# microzed_sd_v0_3_bdec564d.net
KiCad netlist of a schematic drawn in EAGLE
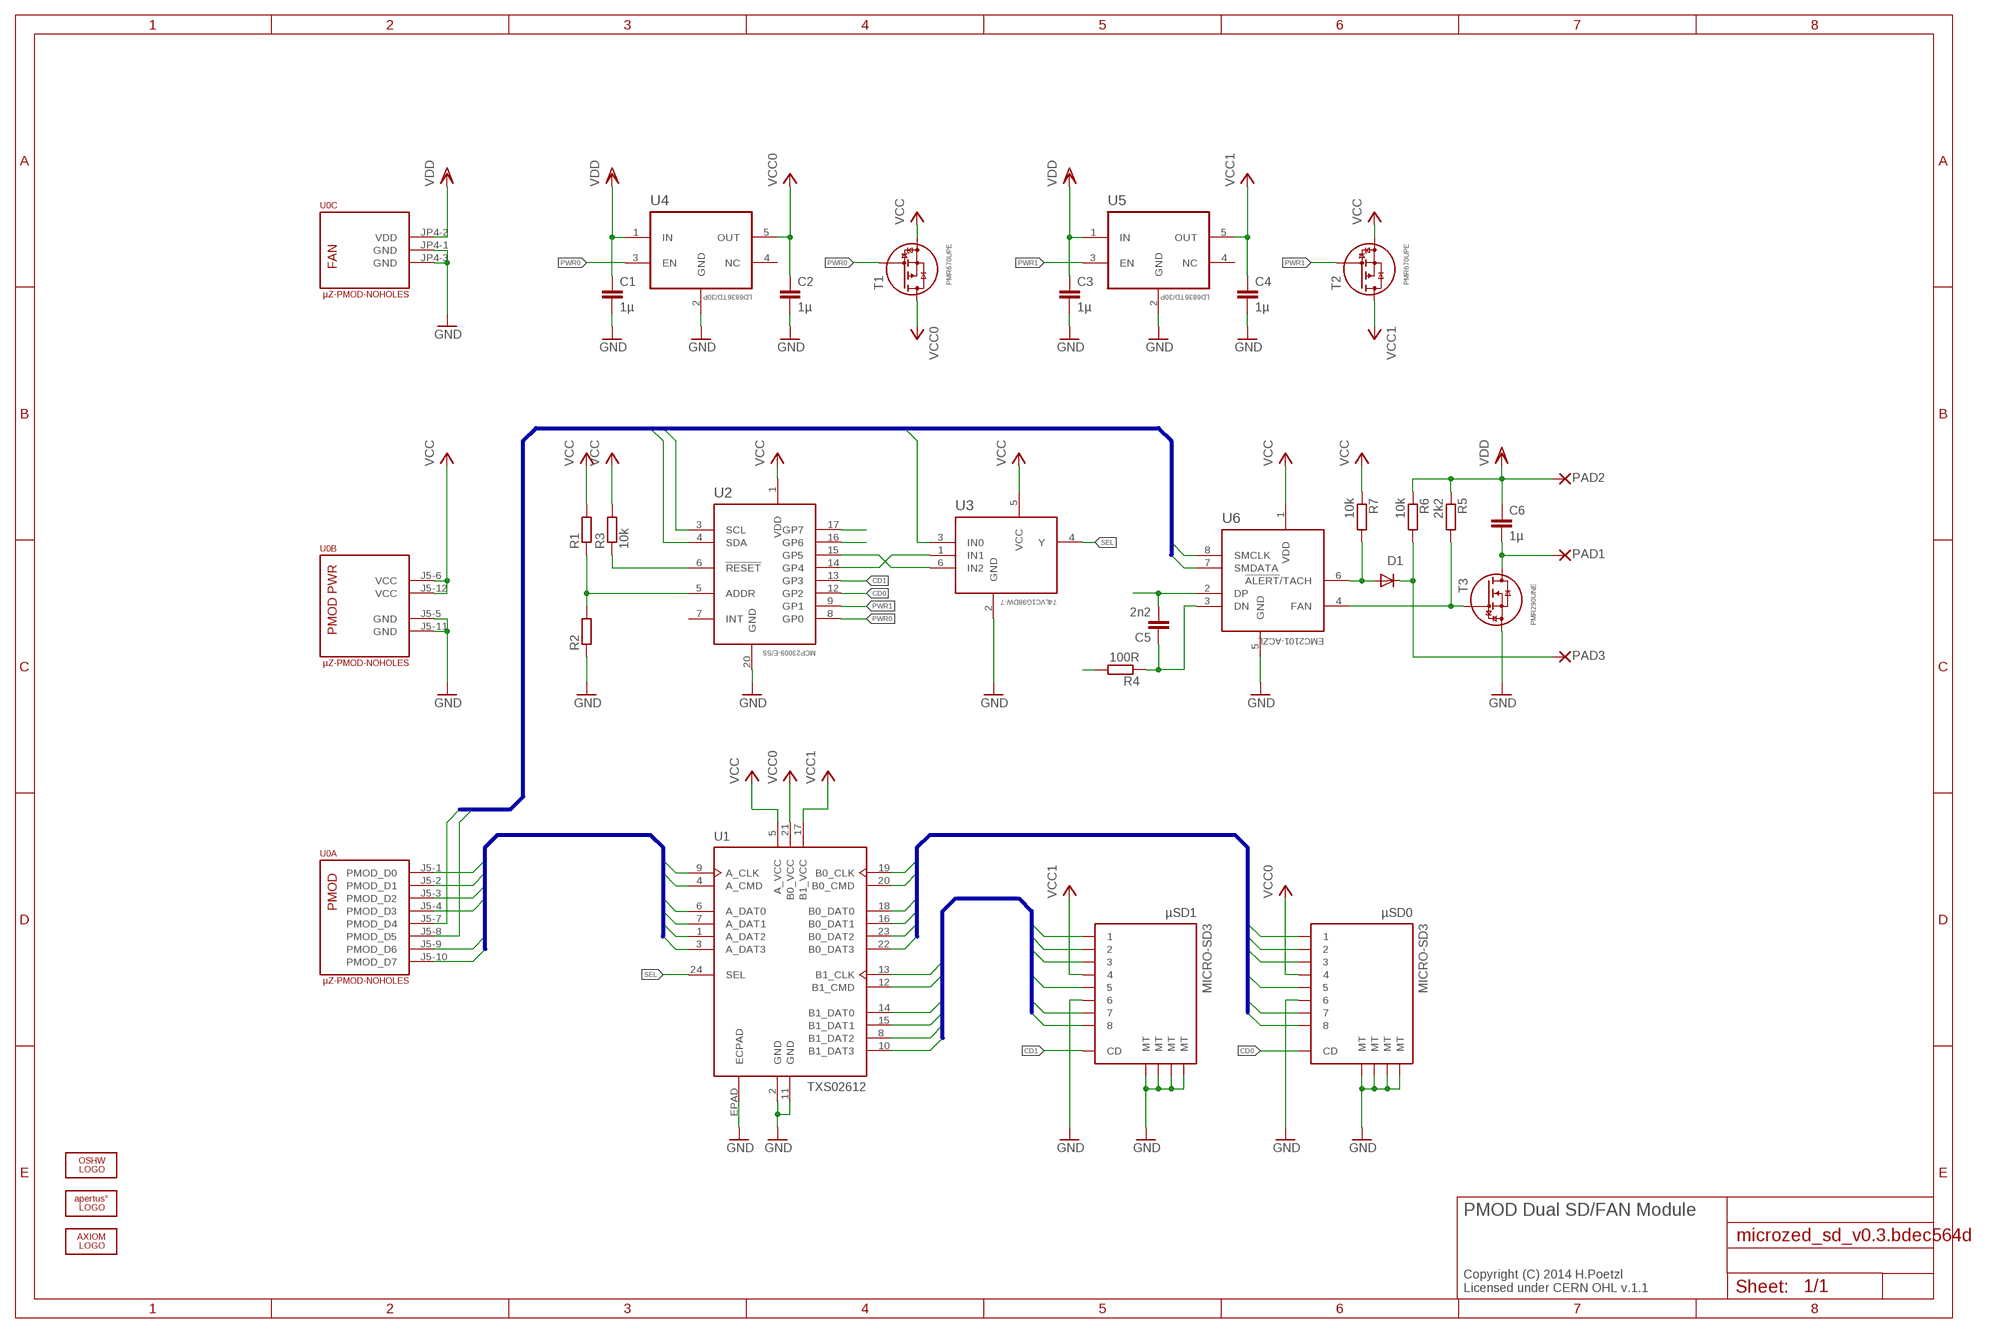
[diagram p0: schematic, sheet 1]

(export (version "E")
  (design (tool "Eeschema 10.0.6"))
  (components
    (comp (ref "C1")
      (value "1µ")
      (footprint "eagle-import:C0402K")
      (libsource (lib "eagle-import") (part "C-EUC0402K"))
    )
    (comp (ref "C2")
      (value "1µ")
      (footprint "eagle-import:C0402K")
      (libsource (lib "eagle-import") (part "C-EUC0402K"))
    )
    (comp (ref "C3")
      (value "1µ")
      (footprint "eagle-import:C0402K")
      (libsource (lib "eagle-import") (part "C-EUC0402K"))
    )
    (comp (ref "C4")
      (value "1µ")
      (footprint "eagle-import:C0402K")
      (libsource (lib "eagle-import") (part "C-EUC0402K"))
    )
    (comp (ref "C5")
      (value "2n2")
      (footprint "eagle-import:C0402K")
      (libsource (lib "eagle-import") (part "C-EUC0402K"))
    )
    (comp (ref "C6")
      (value "1µ")
      (footprint "eagle-import:C0402K")
      (libsource (lib "eagle-import") (part "C-EUC0402K"))
    )
    (comp (ref "D1")
      (value "DIODE-MICROMELF-W")
      (footprint "eagle-import:MICROMELF-W")
      (libsource (lib "eagle-import") (part "DIODE-MICROMELF-W"))
    )
    (comp (ref "LOGO1")
      (value "OSHW_LOGO_FILLX0100-NT")
      (footprint "eagle-import:OSHW_FILLX100_NOTEXT")
      (libsource (lib "eagle-import") (part "OSHW_LOGO_FILLX0100-NT"))
    )
    (comp (ref "PAD1")
      (value "WIREPAD2,15/1,0")
      (footprint "eagle-import:2,15_1,0")
      (libsource (lib "eagle-import") (part "WIREPAD2,15/1,0"))
    )
    (comp (ref "PAD2")
      (value "WIREPAD2,15/1,0")
      (footprint "eagle-import:2,15_1,0")
      (libsource (lib "eagle-import") (part "WIREPAD2,15/1,0"))
    )
    (comp (ref "PAD3")
      (value "WIREPAD2,15/1,0")
      (footprint "eagle-import:2,15_1,0")
      (libsource (lib "eagle-import") (part "WIREPAD2,15/1,0"))
    )
    (comp (ref "R1")
      (value "R-EU_R0603")
      (footprint "eagle-import:R0603")
      (libsource (lib "eagle-import") (part "R-EU_R0603"))
    )
    (comp (ref "R2")
      (value "R-EU_R0603")
      (footprint "eagle-import:R0603")
      (libsource (lib "eagle-import") (part "R-EU_R0603"))
    )
    (comp (ref "R3")
      (value "10k")
      (footprint "eagle-import:R0603")
      (libsource (lib "eagle-import") (part "R-EU_R0603"))
    )
    (comp (ref "R4")
      (value "100R")
      (footprint "eagle-import:R0402")
      (libsource (lib "eagle-import") (part "R-EU_R0402"))
    )
    (comp (ref "R5")
      (value "2k2")
      (footprint "eagle-import:R0402")
      (libsource (lib "eagle-import") (part "R-EU_R0402"))
    )
    (comp (ref "R6")
      (value "10k")
      (footprint "eagle-import:R0402")
      (libsource (lib "eagle-import") (part "R-EU_R0402"))
    )
    (comp (ref "R7")
      (value "10k")
      (footprint "eagle-import:R0402")
      (libsource (lib "eagle-import") (part "R-EU_R0402"))
    )
    (comp (ref "T1")
      (value "PMR670UPE")
      (footprint "eagle-import:SOT416")
      (libsource (lib "eagle-import") (part "PMR670UPE"))
    )
    (comp (ref "T2")
      (value "PMR670UPE")
      (footprint "eagle-import:SOT416")
      (libsource (lib "eagle-import") (part "PMR670UPE"))
    )
    (comp (ref "T3")
      (value "PMR290UNE")
      (footprint "eagle-import:SOT416")
      (libsource (lib "eagle-import") (part "PMR290UNE"))
    )
    (comp (ref "U$1")
      (value "APERTUS_LOGO334X100")
      (footprint "eagle-import:APERTUS_LOGO_334X100")
      (libsource (lib "eagle-import") (part "APERTUS_LOGO334X100"))
    )
    (comp (ref "U$13")
      (value "AXIOM_LOGO525X80")
      (footprint "eagle-import:AXIOM_LOGO_525X80")
      (libsource (lib "eagle-import") (part "AXIOM_LOGO525X80"))
    )
    (comp (ref "U0")
      (value "µZ-PMOD-NOHOLES")
      (footprint "eagle-import:µZ-TOP-NOHOLES")
      (libsource (lib "eagle-import") (part "µZ-PMOD-NOHOLES"))
    )
    (comp (ref "U1")
      (value "TXS02612")
      (footprint "eagle-import:S-PWQFN-N24")
      (libsource (lib "eagle-import") (part "TXS02612"))
    )
    (comp (ref "U2")
      (value "MCP23009-E/SS")
      (footprint "eagle-import:SOP65P780X200-20N")
      (libsource (lib "eagle-import") (part "MCP23009-E/SS"))
    )
    (comp (ref "U3")
      (value "74LVC1G98DW-7")
      (footprint "eagle-import:SOT65P210X110-6N")
      (libsource (lib "eagle-import") (part "74LVC1G98DW-7"))
    )
    (comp (ref "U4")
      (value "LD6836TD/30P")
      (footprint "eagle-import:SOT95P275X110-5N")
      (libsource (lib "eagle-import") (part "LD6836TD/30P"))
    )
    (comp (ref "U5")
      (value "LD6836TD/30P")
      (footprint "eagle-import:SOT95P275X110-5N")
      (libsource (lib "eagle-import") (part "LD6836TD/30P"))
    )
    (comp (ref "U6")
      (value "EMC2101-ACZL")
      (footprint "eagle-import:SOP65P490X110-8N")
      (fields (field (name "MPN") "EMC2101-ACZL-TR "))
      (libsource (lib "eagle-import") (part "EMC2101-ACZL"))
    )
    (comp (ref "µSD0")
      (value "MICRO-SD3")
      (footprint "eagle-import:TF-MICRO-SD_PP3")
      (libsource (lib "eagle-import") (part "MICRO-SD3"))
    )
    (comp (ref "µSD1")
      (value "MICRO-SD3")
      (footprint "eagle-import:TF-MICRO-SD_PP3")
      (libsource (lib "eagle-import") (part "MICRO-SD3"))
    )
  )
  (nets
    (net (code "1") (name "/A_CLK") (class "Default")
      (node (ref "U0") (pin "J5-4") (pinfunction "PMOD_D3_J5-4") (pintype "bidirectional"))
      (node (ref "U1") (pin "9") (pinfunction "A_CLK_9") (pintype "input"))
    )
    (net (code "2") (name "/A_CMD") (class "Default")
      (node (ref "U0") (pin "J5-3") (pinfunction "PMOD_D2_J5-3") (pintype "bidirectional"))
      (node (ref "U1") (pin "4") (pinfunction "A_CMD_4") (pintype "bidirectional"))
    )
    (net (code "3") (name "/A_DAT0") (class "Default")
      (node (ref "U0") (pin "J5-2") (pinfunction "PMOD_D1_J5-2") (pintype "bidirectional"))
      (node (ref "U1") (pin "6") (pinfunction "A_DAT0_6") (pintype "bidirectional"))
    )
    (net (code "4") (name "/A_DAT1") (class "Default")
      (node (ref "U0") (pin "J5-1") (pinfunction "PMOD_D0_J5-1") (pintype "bidirectional"))
      (node (ref "U1") (pin "7") (pinfunction "A_DAT1_7") (pintype "bidirectional"))
    )
    (net (code "5") (name "/A_DAT2") (class "Default")
      (node (ref "U0") (pin "J5-9") (pinfunction "PMOD_D6_J5-9") (pintype "bidirectional"))
      (node (ref "U1") (pin "1") (pinfunction "A_DAT2_1") (pintype "bidirectional"))
    )
    (net (code "6") (name "/A_DAT3") (class "Default")
      (node (ref "U0") (pin "J5-10") (pinfunction "PMOD_D7_J5-10") (pintype "bidirectional"))
      (node (ref "U1") (pin "3") (pinfunction "A_DAT3_3") (pintype "bidirectional"))
    )
    (net (code "7") (name "/B0_CLK") (class "Default")
      (node (ref "U1") (pin "19") (pinfunction "B0_CLK_19") (pintype "output"))
      (node (ref "µSD0") (pin "5") (pinfunction "5_5") (pintype "bidirectional"))
    )
    (net (code "8") (name "/B0_CMD") (class "Default")
      (node (ref "U1") (pin "20") (pinfunction "B0_CMD_20") (pintype "bidirectional"))
      (node (ref "µSD0") (pin "3") (pinfunction "3_3") (pintype "bidirectional"))
    )
    (net (code "9") (name "/B0_DAT0") (class "Default")
      (node (ref "U1") (pin "18") (pinfunction "B0_DAT0_18") (pintype "bidirectional"))
      (node (ref "µSD0") (pin "7") (pinfunction "7_7") (pintype "bidirectional"))
    )
    (net (code "10") (name "/B0_DAT1") (class "Default")
      (node (ref "U1") (pin "16") (pinfunction "B0_DAT1_16") (pintype "bidirectional"))
      (node (ref "µSD0") (pin "8") (pinfunction "8_8") (pintype "bidirectional"))
    )
    (net (code "11") (name "/B0_DAT2") (class "Default")
      (node (ref "U1") (pin "23") (pinfunction "B0_DAT2_23") (pintype "bidirectional"))
      (node (ref "µSD0") (pin "1") (pinfunction "1_1") (pintype "bidirectional"))
    )
    (net (code "12") (name "/B0_DAT3") (class "Default")
      (node (ref "U1") (pin "22") (pinfunction "B0_DAT3_22") (pintype "bidirectional"))
      (node (ref "µSD0") (pin "2") (pinfunction "2_2") (pintype "bidirectional"))
    )
    (net (code "13") (name "/B1_CLK") (class "Default")
      (node (ref "U1") (pin "13") (pinfunction "B1_CLK_13") (pintype "output"))
      (node (ref "µSD1") (pin "5") (pinfunction "5_5") (pintype "bidirectional"))
    )
    (net (code "14") (name "/B1_CMD") (class "Default")
      (node (ref "U1") (pin "12") (pinfunction "B1_CMD_12") (pintype "bidirectional"))
      (node (ref "µSD1") (pin "3") (pinfunction "3_3") (pintype "bidirectional"))
    )
    (net (code "15") (name "/B1_DAT0") (class "Default")
      (node (ref "U1") (pin "14") (pinfunction "B1_DAT0_14") (pintype "bidirectional"))
      (node (ref "µSD1") (pin "7") (pinfunction "7_7") (pintype "bidirectional"))
    )
    (net (code "16") (name "/B1_DAT1") (class "Default")
      (node (ref "U1") (pin "15") (pinfunction "B1_DAT1_15") (pintype "bidirectional"))
      (node (ref "µSD1") (pin "8") (pinfunction "8_8") (pintype "bidirectional"))
    )
    (net (code "17") (name "/B1_DAT2") (class "Default")
      (node (ref "U1") (pin "8") (pinfunction "B1_DAT2_8") (pintype "bidirectional"))
      (node (ref "µSD1") (pin "1") (pinfunction "1_1") (pintype "bidirectional"))
    )
    (net (code "18") (name "/B1_DAT3") (class "Default")
      (node (ref "U1") (pin "10") (pinfunction "B1_DAT3_10") (pintype "bidirectional"))
      (node (ref "µSD1") (pin "2") (pinfunction "2_2") (pintype "bidirectional"))
    )
    (net (code "19") (name "/SCL") (class "Default")
      (node (ref "U0") (pin "J5-7") (pinfunction "PMOD_D4_J5-7") (pintype "bidirectional"))
      (node (ref "U2") (pin "3") (pinfunction "SCL_3") (pintype "input"))
      (node (ref "U6") (pin "8") (pinfunction "SMCLK_8") (pintype "input"))
    )
    (net (code "20") (name "/SDA") (class "Default")
      (node (ref "U0") (pin "J5-8") (pinfunction "PMOD_D5_J5-8") (pintype "bidirectional"))
      (node (ref "U2") (pin "4") (pinfunction "SDA_4") (pintype "bidirectional"))
      (node (ref "U3") (pin "3") (pinfunction "IN0_3") (pintype "input"))
      (node (ref "U6") (pin "7") (pinfunction "SMDATA_7") (pintype "bidirectional"))
    )
    (net (code "21") (name "CD0") (class "Default")
      (node (ref "U2") (pin "12") (pinfunction "GP2_12") (pintype "bidirectional"))
      (node (ref "µSD0") (pin "CD") (pinfunction "CD_CD") (pintype "bidirectional"))
    )
    (net (code "22") (name "CD1") (class "Default")
      (node (ref "U2") (pin "13") (pinfunction "GP3_13") (pintype "bidirectional"))
      (node (ref "µSD1") (pin "CD") (pinfunction "CD_CD") (pintype "bidirectional"))
    )
    (net (code "23") (name "GND") (class "Default")
      (node (ref "C1") (pin "2") (pinfunction "2_2") (pintype "passive"))
      (node (ref "C2") (pin "2") (pinfunction "2_2") (pintype "passive"))
      (node (ref "C3") (pin "2") (pinfunction "2_2") (pintype "passive"))
      (node (ref "C4") (pin "2") (pinfunction "2_2") (pintype "passive"))
      (node (ref "R2") (pin "1") (pinfunction "1_1") (pintype "passive"))
      (node (ref "T3") (pin "2") (pinfunction "S_2") (pintype "passive"))
      (node (ref "U0") (pin "J5-11") (pinfunction "GND_J5-11") (pintype "power_in"))
      (node (ref "U0") (pin "J5-5") (pinfunction "GND_J5-5") (pintype "power_in"))
      (node (ref "U0") (pin "JP4-1") (pinfunction "GND_JP4-1") (pintype "power_in"))
      (node (ref "U0") (pin "JP4-3") (pinfunction "GND_JP4-3") (pintype "power_in"))
      (node (ref "U1") (pin "11") (pinfunction "GND_11") (pintype "power_in"))
      (node (ref "U1") (pin "2") (pinfunction "GND_2") (pintype "power_in"))
      (node (ref "U1") (pin "EPAD") (pinfunction "ECPAD_EPAD") (pintype "power_in"))
      (node (ref "U2") (pin "20") (pinfunction "GND_20") (pintype "power_in"))
      (node (ref "U3") (pin "2") (pinfunction "GND_2") (pintype "passive"))
      (node (ref "U4") (pin "2") (pinfunction "GND_2") (pintype "passive"))
      (node (ref "U5") (pin "2") (pinfunction "GND_2") (pintype "passive"))
      (node (ref "U6") (pin "5") (pinfunction "GND_5") (pintype "power_in"))
      (node (ref "µSD0") (pin "6") (pinfunction "6_6") (pintype "bidirectional"))
      (node (ref "µSD0") (pin "MT1") (pinfunction "MT_MT1") (pintype "power_in"))
      (node (ref "µSD0") (pin "MT2") (pinfunction "MT_MT2") (pintype "power_in"))
      (node (ref "µSD0") (pin "MT3") (pinfunction "MT_MT3") (pintype "power_in"))
      (node (ref "µSD0") (pin "MT4") (pinfunction "MT_MT4") (pintype "power_in"))
      (node (ref "µSD1") (pin "6") (pinfunction "6_6") (pintype "bidirectional"))
      (node (ref "µSD1") (pin "MT1") (pinfunction "MT_MT1") (pintype "power_in"))
      (node (ref "µSD1") (pin "MT2") (pinfunction "MT_MT2") (pintype "power_in"))
      (node (ref "µSD1") (pin "MT3") (pinfunction "MT_MT3") (pintype "power_in"))
      (node (ref "µSD1") (pin "MT4") (pinfunction "MT_MT4") (pintype "power_in"))
    )
    (net (code "24") (name "Net-(PAD1-P)") (class "Default")
      (node (ref "C6") (pin "2") (pinfunction "2_2") (pintype "passive"))
      (node (ref "PAD1") (pin "1") (pinfunction "P_1") (pintype "passive"))
      (node (ref "T3") (pin "3") (pinfunction "D_3") (pintype "passive"))
    )
    (net (code "25") (name "Net-(PAD3-P)") (class "Default")
      (node (ref "D1") (pin "C") (pinfunction "C_C") (pintype "passive"))
      (node (ref "PAD3") (pin "1") (pinfunction "P_1") (pintype "passive"))
      (node (ref "R6") (pin "2") (pinfunction "2_2") (pintype "passive"))
    )
    (net (code "26") (name "Net-(T3-G)") (class "Default")
      (node (ref "R5") (pin "2") (pinfunction "2_2") (pintype "passive"))
      (node (ref "T3") (pin "1") (pinfunction "G_1") (pintype "passive"))
      (node (ref "U6") (pin "4") (pinfunction "FAN_4") (pintype "output"))
    )
    (net (code "27") (name "Net-(U2-ADDR)") (class "Default")
      (node (ref "R1") (pin "1") (pinfunction "1_1") (pintype "passive"))
      (node (ref "R2") (pin "2") (pinfunction "2_2") (pintype "passive"))
      (node (ref "U2") (pin "5") (pinfunction "ADDR_5") (pintype "input"))
    )
    (net (code "28") (name "Net-(U2-GP4)") (class "Default")
      (node (ref "U2") (pin "14") (pinfunction "GP4_14") (pintype "bidirectional"))
      (node (ref "U3") (pin "1") (pinfunction "IN1_1") (pintype "input"))
    )
    (net (code "29") (name "Net-(U2-GP5)") (class "Default")
      (node (ref "U2") (pin "15") (pinfunction "GP5_15") (pintype "bidirectional"))
      (node (ref "U3") (pin "6") (pinfunction "IN2_6") (pintype "input"))
    )
    (net (code "30") (name "Net-(U2-~{RESET})") (class "Default")
      (node (ref "R3") (pin "1") (pinfunction "1_1") (pintype "passive"))
      (node (ref "U2") (pin "6") (pinfunction "~{RESET}_6") (pintype "input"))
    )
    (net (code "31") (name "Net-(U6-DN)") (class "Default")
      (node (ref "C5") (pin "1") (pinfunction "1_1") (pintype "passive"))
      (node (ref "R4") (pin "1") (pinfunction "1_1") (pintype "passive"))
      (node (ref "U6") (pin "3") (pinfunction "DN_3") (pintype "passive"))
    )
    (net (code "32") (name "Net-(U6-DP)") (class "Default")
      (node (ref "C5") (pin "2") (pinfunction "2_2") (pintype "passive"))
      (node (ref "U6") (pin "2") (pinfunction "DP_2") (pintype "passive"))
    )
    (net (code "33") (name "Net-(U6-~{ALERT}{slash}TACH)") (class "Default")
      (node (ref "D1") (pin "A") (pinfunction "A_A") (pintype "passive"))
      (node (ref "R7") (pin "2") (pinfunction "2_2") (pintype "passive"))
      (node (ref "U6") (pin "6") (pinfunction "~{ALERT}/TACH_6") (pintype "bidirectional"))
    )
    (net (code "34") (name "PWR0") (class "Default")
      (node (ref "T1") (pin "1") (pinfunction "G_1") (pintype "passive"))
      (node (ref "U2") (pin "8") (pinfunction "GP0_8") (pintype "bidirectional"))
      (node (ref "U4") (pin "3") (pinfunction "EN_3") (pintype "input"))
    )
    (net (code "35") (name "PWR1") (class "Default")
      (node (ref "T2") (pin "1") (pinfunction "G_1") (pintype "passive"))
      (node (ref "U2") (pin "9") (pinfunction "GP1_9") (pintype "bidirectional"))
      (node (ref "U5") (pin "3") (pinfunction "EN_3") (pintype "input"))
    )
    (net (code "36") (name "SEL") (class "Default")
      (node (ref "U1") (pin "24") (pinfunction "SEL_24") (pintype "input"))
      (node (ref "U3") (pin "4") (pinfunction "Y_4") (pintype "output"))
    )
    (net (code "37") (name "VCC") (class "Default")
      (node (ref "R1") (pin "2") (pinfunction "2_2") (pintype "passive"))
      (node (ref "R3") (pin "2") (pinfunction "2_2") (pintype "passive"))
      (node (ref "R7") (pin "1") (pinfunction "1_1") (pintype "passive"))
      (node (ref "T1") (pin "2") (pinfunction "S_2") (pintype "passive"))
      (node (ref "T2") (pin "2") (pinfunction "S_2") (pintype "passive"))
      (node (ref "U0") (pin "J5-12") (pinfunction "VCC_J5-12") (pintype "power_in"))
      (node (ref "U0") (pin "J5-6") (pinfunction "VCC_J5-6") (pintype "power_in"))
      (node (ref "U1") (pin "5") (pinfunction "A_VCC_5") (pintype "power_in"))
      (node (ref "U2") (pin "1") (pinfunction "VDD_1") (pintype "power_in"))
      (node (ref "U3") (pin "5") (pinfunction "VCC_5") (pintype "power_in"))
      (node (ref "U6") (pin "1") (pinfunction "VDD_1") (pintype "power_in"))
    )
    (net (code "38") (name "VCC0") (class "Default")
      (node (ref "C2") (pin "1") (pinfunction "1_1") (pintype "passive"))
      (node (ref "T1") (pin "3") (pinfunction "D_3") (pintype "passive"))
      (node (ref "U1") (pin "21") (pinfunction "B0_VCC_21") (pintype "power_in"))
      (node (ref "U4") (pin "5") (pinfunction "OUT_5") (pintype "output"))
      (node (ref "µSD0") (pin "4") (pinfunction "4_4") (pintype "bidirectional"))
    )
    (net (code "39") (name "VCC1") (class "Default")
      (node (ref "C4") (pin "1") (pinfunction "1_1") (pintype "passive"))
      (node (ref "T2") (pin "3") (pinfunction "D_3") (pintype "passive"))
      (node (ref "U1") (pin "17") (pinfunction "B1_VCC_17") (pintype "power_in"))
      (node (ref "U5") (pin "5") (pinfunction "OUT_5") (pintype "output"))
      (node (ref "µSD1") (pin "4") (pinfunction "4_4") (pintype "bidirectional"))
    )
    (net (code "40") (name "VDD") (class "Default")
      (node (ref "C1") (pin "1") (pinfunction "1_1") (pintype "passive"))
      (node (ref "C3") (pin "1") (pinfunction "1_1") (pintype "passive"))
      (node (ref "C6") (pin "1") (pinfunction "1_1") (pintype "passive"))
      (node (ref "PAD2") (pin "1") (pinfunction "P_1") (pintype "passive"))
      (node (ref "R5") (pin "1") (pinfunction "1_1") (pintype "passive"))
      (node (ref "R6") (pin "1") (pinfunction "1_1") (pintype "passive"))
      (node (ref "U0") (pin "JP4-2") (pinfunction "VDD_JP4-2") (pintype "power_in"))
      (node (ref "U4") (pin "1") (pinfunction "IN_1") (pintype "input"))
      (node (ref "U5") (pin "1") (pinfunction "IN_1") (pintype "input"))
    )
    (net (code "41") (name "unconnected-(R4-Pad2)") (class "Default")
      (node (ref "R4") (pin "2") (pinfunction "2_2") (pintype "passive"))
    )
    (net (code "42") (name "unconnected-(U2-GP6-Pad16)") (class "Default")
      (node (ref "U2") (pin "16") (pinfunction "GP6_16") (pintype "bidirectional"))
    )
    (net (code "43") (name "unconnected-(U2-GP7-Pad17)") (class "Default")
      (node (ref "U2") (pin "17") (pinfunction "GP7_17") (pintype "bidirectional"))
    )
    (net (code "44") (name "unconnected-(U2-INT-Pad7)") (class "Default")
      (node (ref "U2") (pin "7") (pinfunction "INT_7") (pintype "output"))
    )
    (net (code "45") (name "unconnected-(U4-NC-Pad4)") (class "Default")
      (node (ref "U4") (pin "4") (pinfunction "NC_4") (pintype "no_connect"))
    )
    (net (code "46") (name "unconnected-(U5-NC-Pad4)") (class "Default")
      (node (ref "U5") (pin "4") (pinfunction "NC_4") (pintype "no_connect"))
    )
  )
)
